# USB.net
KiCad netlist of a schematic drawn in Altium Designer
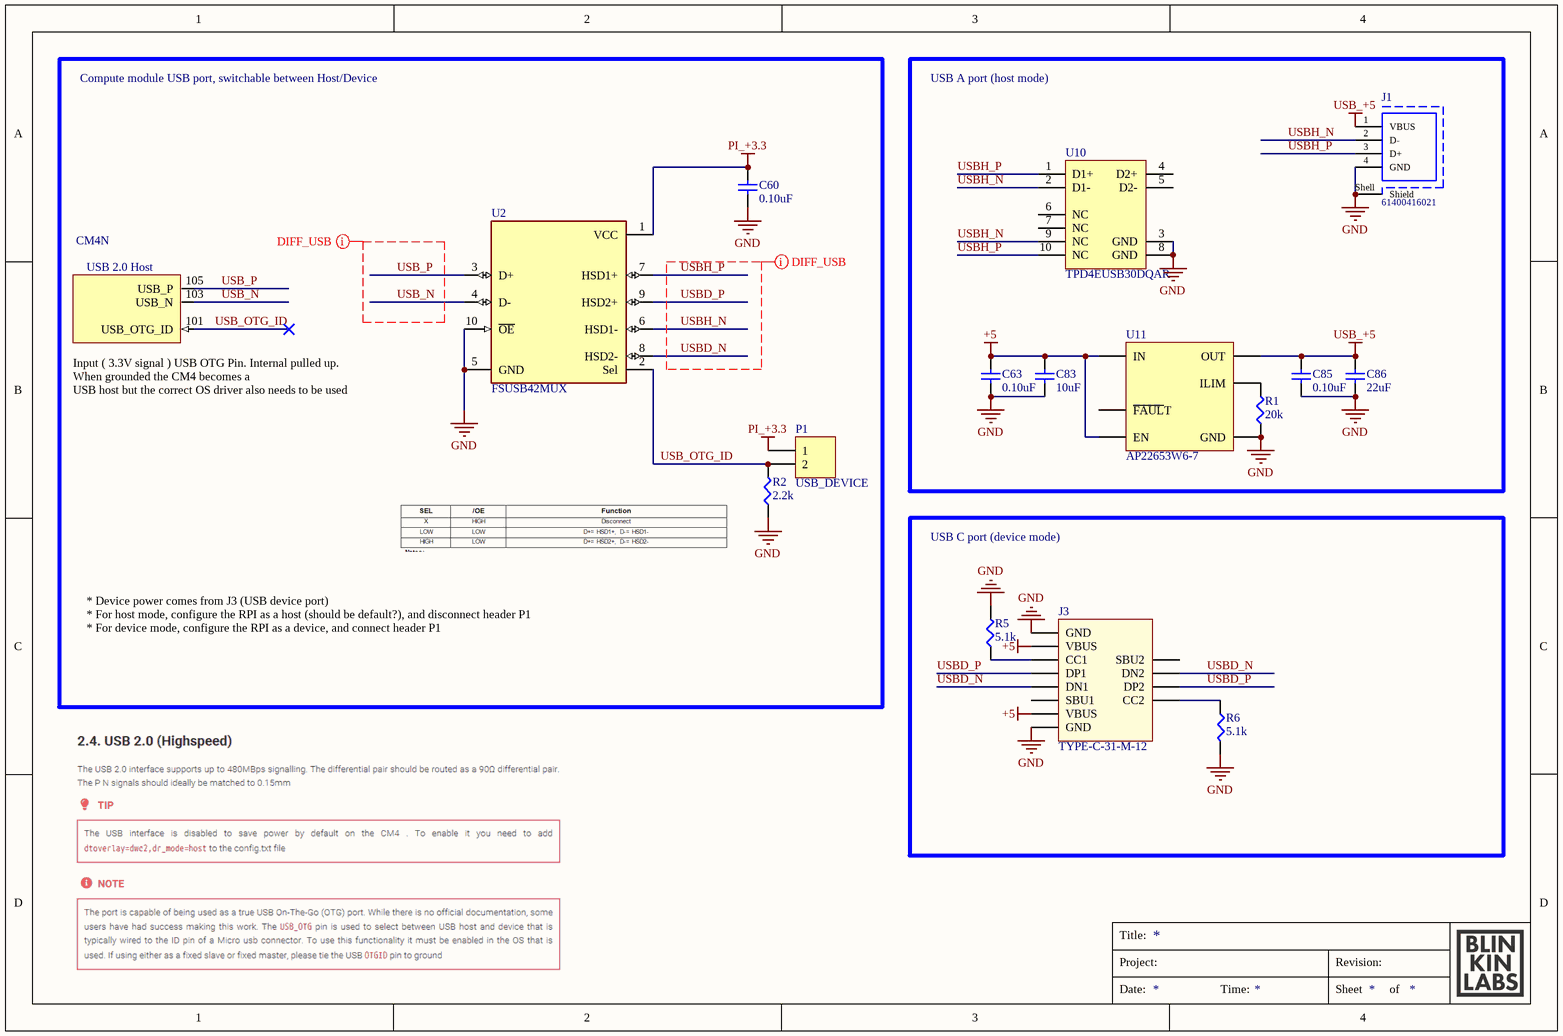
[diagram p0: USB.SchDoc]

(export (version "E")
  (design (tool "Eeschema 10.0.6"))
  (components
    (comp (ref "C60")
      (value "0.10uF")
      (footprint "CAPC1005X06L")
      (description "CAP CER 0.1UF 10V X5R 0402")
      (fields
        (field (name "PARTNUMBER") "GRM155R61A104KA01D")
        (field (name "DIGI-KEY PART NUMBER") "490-1318-1-ND")
      )
      (libsource (lib "cap_murata") (part "CAPACITOR"))
    )
    (comp (ref "C63")
      (value "0.10uF")
      (footprint "CAPC1005X06L")
      (description "CAP CER 0.1UF 10V X5R 0402")
      (fields
        (field (name "PARTNUMBER") "GRM155R61A104KA01D")
        (field (name "DIGI-KEY PART NUMBER") "490-1318-1-ND")
      )
      (libsource (lib "cap_murata") (part "CAPACITOR"))
    )
    (comp (ref "C83")
      (value "10uF")
      (footprint "CAPC2012X10L")
      (description "CAP CER 10UF 10V X7R 0805")
      (fields
        (field (name "PARTNUMBER") "GRM21BR71A106KE51L")
        (field (name "DIGI-KEY PART NUMBER") "490-3905-1-ND")
      )
      (libsource (lib "cap_murata") (part "CAPACITOR"))
    )
    (comp (ref "C85")
      (value "0.10uF")
      (footprint "CAPC1005X06L")
      (description "CAP CER 0.1UF 10V X5R 0402")
      (fields
        (field (name "PARTNUMBER") "GRM155R61A104KA01D")
        (field (name "DIGI-KEY PART NUMBER") "490-1318-1-ND")
      )
      (libsource (lib "cap_murata") (part "CAPACITOR"))
    )
    (comp (ref "C86")
      (value "22uF")
      (footprint "CAPC2012X10L")
      (description "CAP CER 22UF 10V X5R 0805")
      (fields
        (field (name "PARTNUMBER") "GRM219R61A226MEA0D")
        (field (name "DIGI-KEY PART NUMBER") "490-9951-1-ND")
      )
      (libsource (lib "cap_murata") (part "CAPACITOR"))
    )
    (comp (ref "CM4")
      (value "Raspberry Pi Compute Module 4")
      (footprint "CM4-F40C-100DS-0.4v_1.5mm_0mm")
      (description "Raspberry Pi Compute Module 4 by Amornthep Phunsin")
      (libsource (lib "CM4") (part "CM4"))
    )
    (comp (ref "J1")
      (value "61400416021")
      (footprint "61400416021")
      (description "USB 2.0 Type A Receptacle WR-COM, Horizontal, THT")
      (fields (field (name "MANUFACTURER") "Wurth Elektronik") (field (name "PUBLISHER") "WurthElektronik"))
      (libsource (lib "Altium Content Vault") (part "WE-USB-4-1SHLD"))
    )
    (comp (ref "J3")
      (value "TYPE-C-31-M-12")
      (footprint "TYPE-C-31-M-12")
      (description "USB Connector TYPE-C-31-M-12 Female 16P SMD")
      (fields (field (name "MANUFACTURER") "HRO"))
      (libsource (lib "Blinkinlabs") (part "TYPE-C-31-M-12"))
    )
    (comp (ref "P1")
      (value "USB_DEVICE")
      (footprint "HDR1X2")
      (description "Header, 2-Pin")
      (fields (field (name "PUBLISHER") "Altium Limited"))
      (libsource (lib "Miscellaneous Connectors") (part "Header 2"))
    )
    (comp (ref "R1")
      (value "20k")
      (footprint "ERJ2G(0402)_L")
      (description "RES SMD 20K OHM 1% 1/10W 0402")
      (fields
        (field (name "PARTNUMBER") "ERJ-2RKF2002X")
        (field (name "DIGI-KEY PART NUMBER") "P20.0KLCT-ND")
      )
      (libsource (lib "res_panasonic_erj_xls") (part "RESISTOR"))
    )
    (comp (ref "R2")
      (value "2.2k")
      (footprint "ERJ2G(0402)_L")
      (description "RES SMD 2.2K OHM 1% 1/10W 0402")
      (fields
        (field (name "PARTNUMBER") "ERJ-2RKF2201X")
        (field (name "DIGI-KEY PART NUMBER") "P2.20KLCT-ND")
      )
      (libsource (lib "res_panasonic_erj_xls") (part "RESISTOR"))
    )
    (comp (ref "R5")
      (value "5.1k")
      (footprint "ERJ2G(0402)_N")
      (description "RES SMD 5.1K OHM 1% 1/10W 0402")
      (fields
        (field (name "PARTNUMBER") "ERJ-2RKF5101X")
        (field (name "DIGI-KEY PART NUMBER") "P5.10KLCT-ND")
      )
      (libsource (lib "res_panasonic_erj_xls") (part "RESISTOR"))
    )
    (comp (ref "R6")
      (value "5.1k")
      (footprint "ERJ2G(0402)_N")
      (description "RES SMD 5.1K OHM 1% 1/10W 0402")
      (fields
        (field (name "PARTNUMBER") "ERJ-2RKF5101X")
        (field (name "DIGI-KEY PART NUMBER") "P5.10KLCT-ND")
      )
      (libsource (lib "res_panasonic_erj_xls") (part "RESISTOR"))
    )
    (comp (ref "U2")
      (value "FSUSB42MUX")
      (footprint "FP-846AP-MFG")
      (description "IC USB SWITCH DPDT 10MSOP")
      (fields (field (name "VOLTAGE") "4.3V"))
      (libsource (lib "Altium Content Vault") (part "e0bd5e1b4e0e4edc77f3356c64bf8f9"))
    )
    (comp (ref "U10")
      (value "TPD4EUSB30DQAR")
      (footprint "DQA0010A_V")
      (fields (field (name "MANUFACTURER") "Texas Instruments"))
      (libsource (lib "Altium Content Vault") (part "TI-TPD4EUSB30-SON_DQA-10"))
    )
    (comp (ref "U11")
      (value "AP22653W6-7")
      (footprint "SOT95P280X145-6N-5")
      (description "LOAD SWITCH,SOT26,T&R,3K")
      (fields
        (field (name "MANUFACTURER") "Diodes Incorporated")
        (field (name "DIGIKEY PARTNUMBER") "31-AP22653W6-7TR-ND")
      )
      (libsource (lib "Blinkinlabs") (part "AP22653W6-7"))
    )
  )
  (nets
    (net (code "1") (name "+5") (class "Default")
      (node (ref "C63") (pin "2") (pinfunction "2_2") (pintype "passive"))
      (node (ref "C83") (pin "1") (pinfunction "1_1") (pintype "passive"))
      (node (ref "J3") (pin "A4/B9") (pinfunction "VBUS_A4/B9") (pintype "passive"))
      (node (ref "J3") (pin "A9/B4") (pinfunction "VBUS_A9/B4") (pintype "passive"))
      (node (ref "U11") (pin "1") (pinfunction "IN_1") (pintype "passive"))
      (node (ref "U11") (pin "3") (pinfunction "EN_3") (pintype "passive"))
    )
    (net (code "2") (name "/USBD_N") (class "Default")
      (node (ref "J3") (pin "A7") (pinfunction "DN1_A7") (pintype "passive"))
      (node (ref "J3") (pin "B7") (pinfunction "DN2_B7") (pintype "passive"))
      (node (ref "U2") (pin "8") (pinfunction "HSD2-_8") (pintype "bidirectional"))
    )
    (net (code "3") (name "/USBD_P") (class "Default")
      (node (ref "J3") (pin "A6") (pinfunction "DP1_A6") (pintype "passive"))
      (node (ref "J3") (pin "B6") (pinfunction "DP2_B6") (pintype "passive"))
      (node (ref "U2") (pin "9") (pinfunction "HSD2+_9") (pintype "bidirectional"))
    )
    (net (code "4") (name "/USBH_N") (class "Default")
      (node (ref "J1") (pin "2") (pinfunction "D-_2") (pintype "passive"))
      (node (ref "U10") (pin "2") (pinfunction "D1-_2") (pintype "passive"))
      (node (ref "U10") (pin "9") (pinfunction "NC_9") (pintype "passive"))
      (node (ref "U2") (pin "6") (pinfunction "HSD1-_6") (pintype "bidirectional"))
    )
    (net (code "5") (name "/USBH_P") (class "Default")
      (node (ref "J1") (pin "3") (pinfunction "D+_3") (pintype "passive"))
      (node (ref "U10") (pin "1") (pinfunction "D1+_1") (pintype "passive"))
      (node (ref "U10") (pin "10") (pinfunction "NC_10") (pintype "passive"))
      (node (ref "U2") (pin "7") (pinfunction "HSD1+_7") (pintype "bidirectional"))
    )
    (net (code "6") (name "/USB_N") (class "Default")
      (node (ref "CM4") (pin "103") (pinfunction "USB_N_103") (pintype "passive"))
      (node (ref "U2") (pin "4") (pinfunction "D-_4") (pintype "bidirectional"))
    )
    (net (code "7") (name "/USB_OTG_ID") (class "Default")
      (node (ref "CM4") (pin "101") (pinfunction "USB_OTG_ID_101") (pintype "input"))
      (node (ref "P1") (pin "2") (pinfunction "2_2") (pintype "passive"))
      (node (ref "R2") (pin "2") (pinfunction "2_2") (pintype "passive"))
      (node (ref "U2") (pin "2") (pinfunction "Sel_2") (pintype "passive"))
    )
    (net (code "8") (name "/USB_P") (class "Default")
      (node (ref "CM4") (pin "105") (pinfunction "USB_P_105") (pintype "passive"))
      (node (ref "U2") (pin "3") (pinfunction "D+_3") (pintype "bidirectional"))
    )
    (net (code "9") (name "GND") (class "Default")
      (node (ref "C60") (pin "1") (pinfunction "1_1") (pintype "passive"))
      (node (ref "C63") (pin "1") (pinfunction "1_1") (pintype "passive"))
      (node (ref "C83") (pin "2") (pinfunction "2_2") (pintype "passive"))
      (node (ref "C85") (pin "1") (pinfunction "1_1") (pintype "passive"))
      (node (ref "C86") (pin "2") (pinfunction "2_2") (pintype "passive"))
      (node (ref "J1") (pin "4") (pinfunction "GND_4") (pintype "passive"))
      (node (ref "J1") (pin "Shell") (pinfunction "Shield_Shell") (pintype "passive"))
      (node (ref "J3") (pin "A1/B12") (pinfunction "GND_A1/B12") (pintype "passive"))
      (node (ref "J3") (pin "A12/B1") (pinfunction "GND_A12/B1") (pintype "passive"))
      (node (ref "R1") (pin "1") (pinfunction "1_1") (pintype "passive"))
      (node (ref "R2") (pin "1") (pinfunction "1_1") (pintype "passive"))
      (node (ref "R5") (pin "2") (pinfunction "2_2") (pintype "passive"))
      (node (ref "R6") (pin "2") (pinfunction "2_2") (pintype "passive"))
      (node (ref "U10") (pin "3") (pinfunction "GND_3") (pintype "power_in"))
      (node (ref "U10") (pin "8") (pinfunction "GND_8") (pintype "power_in"))
      (node (ref "U11") (pin "2") (pinfunction "GND_2") (pintype "passive"))
      (node (ref "U2") (pin "10") (pinfunction "~{OE}_10") (pintype "input"))
      (node (ref "U2") (pin "5") (pinfunction "GND_5") (pintype "power_in"))
    )
    (net (code "10") (name "Net-(J3-CC1)") (class "Default")
      (node (ref "J3") (pin "A5") (pinfunction "CC1_A5") (pintype "passive"))
      (node (ref "R5") (pin "1") (pinfunction "1_1") (pintype "passive"))
    )
    (net (code "11") (name "Net-(J3-CC2)") (class "Default")
      (node (ref "J3") (pin "B5") (pinfunction "CC2_B5") (pintype "passive"))
      (node (ref "R6") (pin "1") (pinfunction "1_1") (pintype "passive"))
    )
    (net (code "12") (name "Net-(U11-ILIM)") (class "Default")
      (node (ref "R1") (pin "2") (pinfunction "2_2") (pintype "passive"))
      (node (ref "U11") (pin "5") (pinfunction "ILIM_5") (pintype "passive"))
    )
    (net (code "13") (name "PI_+3.3") (class "Default")
      (node (ref "C60") (pin "2") (pinfunction "2_2") (pintype "passive"))
      (node (ref "P1") (pin "1") (pinfunction "1_1") (pintype "passive"))
      (node (ref "U2") (pin "1") (pinfunction "VCC_1") (pintype "power_in"))
    )
    (net (code "14") (name "USB_+5") (class "Default")
      (node (ref "C85") (pin "2") (pinfunction "2_2") (pintype "passive"))
      (node (ref "C86") (pin "1") (pinfunction "1_1") (pintype "passive"))
      (node (ref "J1") (pin "1") (pinfunction "VBUS_1") (pintype "passive"))
      (node (ref "U11") (pin "6") (pinfunction "OUT_6") (pintype "passive"))
    )
    (net (code "15") (name "unconnected-(J3-SBU1-PadA8)") (class "Default")
      (node (ref "J3") (pin "A8") (pinfunction "SBU1_A8") (pintype "passive"))
    )
    (net (code "16") (name "unconnected-(J3-SBU2-PadB8)") (class "Default")
      (node (ref "J3") (pin "B8") (pinfunction "SBU2_B8") (pintype "passive"))
    )
    (net (code "17") (name "unconnected-(U10-D2+-Pad4)") (class "Default")
      (node (ref "U10") (pin "4") (pinfunction "D2+_4") (pintype "passive"))
    )
    (net (code "18") (name "unconnected-(U10-D2--Pad5)") (class "Default")
      (node (ref "U10") (pin "5") (pinfunction "D2-_5") (pintype "passive"))
    )
    (net (code "19") (name "unconnected-(U10-NC-Pad6)") (class "Default")
      (node (ref "U10") (pin "6") (pinfunction "NC_6") (pintype "passive"))
    )
    (net (code "20") (name "unconnected-(U10-NC-Pad7)") (class "Default")
      (node (ref "U10") (pin "7") (pinfunction "NC_7") (pintype "passive"))
    )
    (net (code "21") (name "unconnected-(U11-~{FAUL}T-Pad4)") (class "Default")
      (node (ref "U11") (pin "4") (pinfunction "~{FAUL}T_4") (pintype "passive"))
    )
  )
)
